# MWInjector.net
KiCad netlist of a schematic drawn in EAGLE
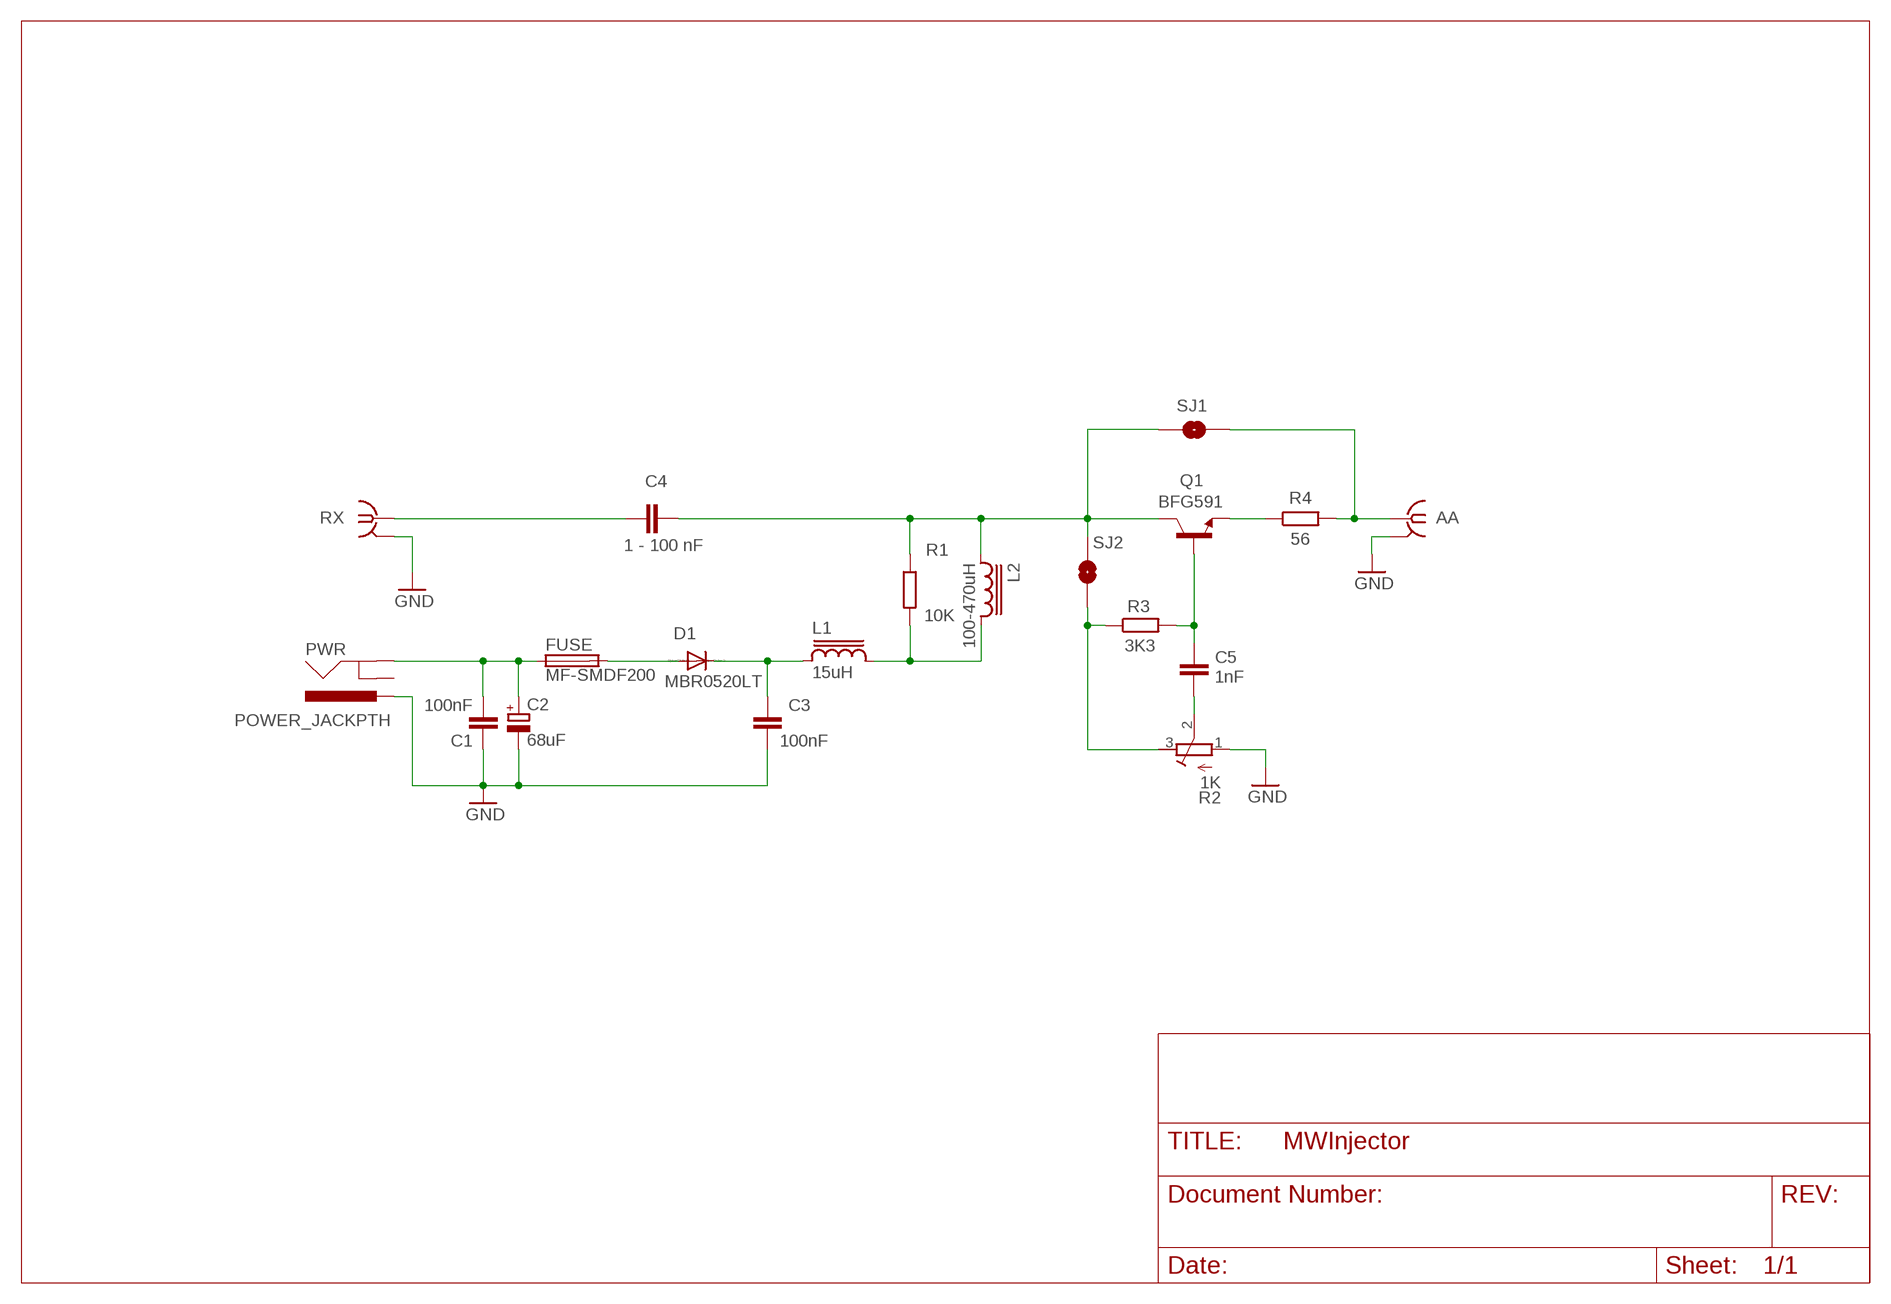
[diagram p0: schematic, sheet 1]

(export (version "E")
  (design (tool "Eeschema 10.0.6"))
  (components
    (comp (ref "AA")
      (value "SMA-142-0701-851/861")
      (footprint "eagle-import:J502-ND-142-0701-851_861")
      (fields (field (name "MF") "JOHNSON COMPONENTS") (field (name "MPN") "142-0701-851"))
      (libsource (lib "eagle-import") (part "SMA-142-0701-851/861"))
    )
    (comp (ref "C1")
      (value "100nF")
      (footprint "eagle-import:C1206")
      (libsource (lib "eagle-import") (part "C-EUC1206"))
    )
    (comp (ref "C2")
      (value "68uF")
      (footprint "eagle-import:SMC_C")
      (libsource (lib "eagle-import") (part "CPOL-EUSMCC"))
    )
    (comp (ref "C3")
      (value "100nF")
      (footprint "eagle-import:C1206")
      (libsource (lib "eagle-import") (part "C-EUC1206"))
    )
    (comp (ref "C4")
      (value "1 - 100 nF")
      (footprint "eagle-import:C1206")
      (libsource (lib "eagle-import") (part "C-EUC1206"))
    )
    (comp (ref "C5")
      (value "1nF")
      (footprint "eagle-import:C1206")
      (libsource (lib "eagle-import") (part "C-EUC1206"))
    )
    (comp (ref "D1")
      (value "MBR0520LT")
      (footprint "eagle-import:SOD123")
      (libsource (lib "eagle-import") (part "MBR0520LT"))
    )
    (comp (ref "FUSE")
      (value "MF-SMDF200")
      (footprint "eagle-import:MF-SMDF050")
      (libsource (lib "eagle-import") (part "MF-SMDF200"))
    )
    (comp (ref "L1")
      (value "15uH")
      (footprint "eagle-import:CDRH6D")
      (libsource (lib "eagle-import") (part "CDRH6D38"))
    )
    (comp (ref "L2")
      (value "100-470uH")
      (footprint "eagle-import:CDRH104R")
      (libsource (lib "eagle-import") (part "CDRH104R"))
    )
    (comp (ref "PWR")
      (value "POWER_JACKPTH")
      (footprint "eagle-import:POWER_JACK_PTH")
      (libsource (lib "eagle-import") (part "POWER_JACKPTH"))
    )
    (comp (ref "Q1")
      (value "BFG591")
      (footprint "eagle-import:SOT223")
      (libsource (lib "eagle-import") (part "BFG591"))
    )
    (comp (ref "R1")
      (value "10K")
      (footprint "eagle-import:R1206")
      (libsource (lib "eagle-import") (part "R-EU_R1206"))
    )
    (comp (ref "R2")
      (value "1K")
      (footprint "eagle-import:RTRIM3202")
      (libsource (lib "eagle-import") (part "R-TRIMM3202"))
    )
    (comp (ref "R3")
      (value "3K3")
      (footprint "eagle-import:R1206")
      (libsource (lib "eagle-import") (part "R-EU_R1206"))
    )
    (comp (ref "R4")
      (value "56")
      (footprint "eagle-import:R2512")
      (libsource (lib "eagle-import") (part "R-EU_R2512"))
    )
    (comp (ref "RX")
      (value "SMA-142-0701-851/861")
      (footprint "eagle-import:J502-ND-142-0701-851_861")
      (fields (field (name "MF") "JOHNSON COMPONENTS") (field (name "MPN") "142-0701-851"))
      (libsource (lib "eagle-import") (part "con-coax_133_SMA-142-0701-851/861"))
    )
    (comp (ref "SJ1")
      (value "SOLDERJUMPERNO")
      (footprint "eagle-import:SJ_2S-NO")
      (libsource (lib "eagle-import") (part "SOLDERJUMPERNO"))
    )
    (comp (ref "SJ2")
      (value "SOLDERJUMPERNO")
      (footprint "eagle-import:SJ_2S-NO")
      (libsource (lib "eagle-import") (part "SOLDERJUMPERNO"))
    )
  )
  (nets
    (net (code "1") (name "GND") (class "Default")
      (node (ref "AA") (pin "G@1") (pinfunction "2_G@1") (pintype "passive"))
      (node (ref "AA") (pin "G@2") (pinfunction "2_G@2") (pintype "passive"))
      (node (ref "AA") (pin "G@3") (pinfunction "2_G@3") (pintype "passive"))
      (node (ref "AA") (pin "G@4") (pinfunction "2_G@4") (pintype "passive"))
      (node (ref "C1") (pin "1") (pinfunction "1_1") (pintype "passive"))
      (node (ref "C2") (pin "-") (pinfunction "-_-") (pintype "passive"))
      (node (ref "C3") (pin "1") (pinfunction "1_1") (pintype "passive"))
      (node (ref "PWR") (pin "PWR") (pinfunction "PWR_PWR") (pintype "bidirectional"))
      (node (ref "R2") (pin "1") (pinfunction "A_1") (pintype "passive"))
      (node (ref "RX") (pin "G@1") (pinfunction "2_G@1") (pintype "passive"))
      (node (ref "RX") (pin "G@2") (pinfunction "2_G@2") (pintype "passive"))
      (node (ref "RX") (pin "G@3") (pinfunction "2_G@3") (pintype "passive"))
      (node (ref "RX") (pin "G@4") (pinfunction "2_G@4") (pintype "passive"))
    )
    (net (code "2") (name "Net-(AA-Pad1)") (class "Default")
      (node (ref "AA") (pin "1") (pinfunction "1_1") (pintype "passive"))
      (node (ref "R4") (pin "2") (pinfunction "2_2") (pintype "passive"))
      (node (ref "SJ1") (pin "2") (pinfunction "2_2") (pintype "passive"))
    )
    (net (code "3") (name "Net-(C1-Pad2)") (class "Default")
      (node (ref "C1") (pin "2") (pinfunction "2_2") (pintype "passive"))
      (node (ref "C2") (pin "+") (pinfunction "+_+") (pintype "passive"))
      (node (ref "FUSE") (pin "1") (pinfunction "1_1") (pintype "passive"))
      (node (ref "PWR") (pin "GND") (pinfunction "GND_GND") (pintype "bidirectional"))
    )
    (net (code "4") (name "Net-(C3-Pad2)") (class "Default")
      (node (ref "C3") (pin "2") (pinfunction "2_2") (pintype "passive"))
      (node (ref "D1") (pin "C") (pinfunction "C_C") (pintype "passive"))
      (node (ref "L1") (pin "1") (pinfunction "1_1") (pintype "passive"))
    )
    (net (code "5") (name "Net-(C4-Pad2)") (class "Default")
      (node (ref "C4") (pin "2") (pinfunction "2_2") (pintype "passive"))
      (node (ref "RX") (pin "1") (pinfunction "1_1") (pintype "passive"))
    )
    (net (code "6") (name "Net-(D1-PadA)") (class "Default")
      (node (ref "D1") (pin "A") (pinfunction "A_A") (pintype "passive"))
      (node (ref "FUSE") (pin "2") (pinfunction "2_2") (pintype "passive"))
    )
    (net (code "7") (name "Net-(L1-Pad2)") (class "Default")
      (node (ref "L1") (pin "2") (pinfunction "2_2") (pintype "passive"))
      (node (ref "L2") (pin "2") (pinfunction "2_2") (pintype "passive"))
      (node (ref "R1") (pin "2") (pinfunction "2_2") (pintype "passive"))
    )
    (net (code "8") (name "Net-(Q1-B)") (class "Default")
      (node (ref "C5") (pin "2") (pinfunction "2_2") (pintype "passive"))
      (node (ref "Q1") (pin "2") (pinfunction "B_2") (pintype "passive"))
      (node (ref "R3") (pin "2") (pinfunction "2_2") (pintype "passive"))
    )
    (net (code "9") (name "Net-(Q1-C)") (class "Default")
      (node (ref "C4") (pin "1") (pinfunction "1_1") (pintype "passive"))
      (node (ref "L2") (pin "1") (pinfunction "1_1") (pintype "passive"))
      (node (ref "Q1") (pin "4") (pinfunction "C_4") (pintype "passive"))
      (node (ref "R1") (pin "1") (pinfunction "1_1") (pintype "passive"))
      (node (ref "SJ1") (pin "1") (pinfunction "1_1") (pintype "passive"))
      (node (ref "SJ2") (pin "2") (pinfunction "2_2") (pintype "passive"))
    )
    (net (code "10") (name "Net-(Q1-E-Pad1)") (class "Default")
      (node (ref "Q1") (pin "1") (pinfunction "E_1") (pintype "passive"))
      (node (ref "Q1") (pin "3") (pinfunction "E_3") (pintype "passive"))
      (node (ref "R4") (pin "1") (pinfunction "1_1") (pintype "passive"))
    )
    (net (code "11") (name "Net-(R2-E)") (class "Default")
      (node (ref "R2") (pin "3") (pinfunction "E_3") (pintype "passive"))
      (node (ref "R3") (pin "1") (pinfunction "1_1") (pintype "passive"))
      (node (ref "SJ2") (pin "1") (pinfunction "1_1") (pintype "passive"))
    )
    (net (code "12") (name "Net-(R2-S)") (class "Default")
      (node (ref "C5") (pin "1") (pinfunction "1_1") (pintype "passive"))
      (node (ref "R2") (pin "2") (pinfunction "S_2") (pintype "passive"))
    )
    (net (code "13") (name "unconnected-(PWR-PadGNDBREAK)") (class "Default")
      (node (ref "PWR") (pin "GNDBREAK") (pinfunction "GNDBREAK_GNDBREAK") (pintype "bidirectional"))
    )
  )
)
